# SCH_ZeeMini_-_2652p_Board_2021-08-10.net
KiCad netlist of a schematic drawn in EasyEDA
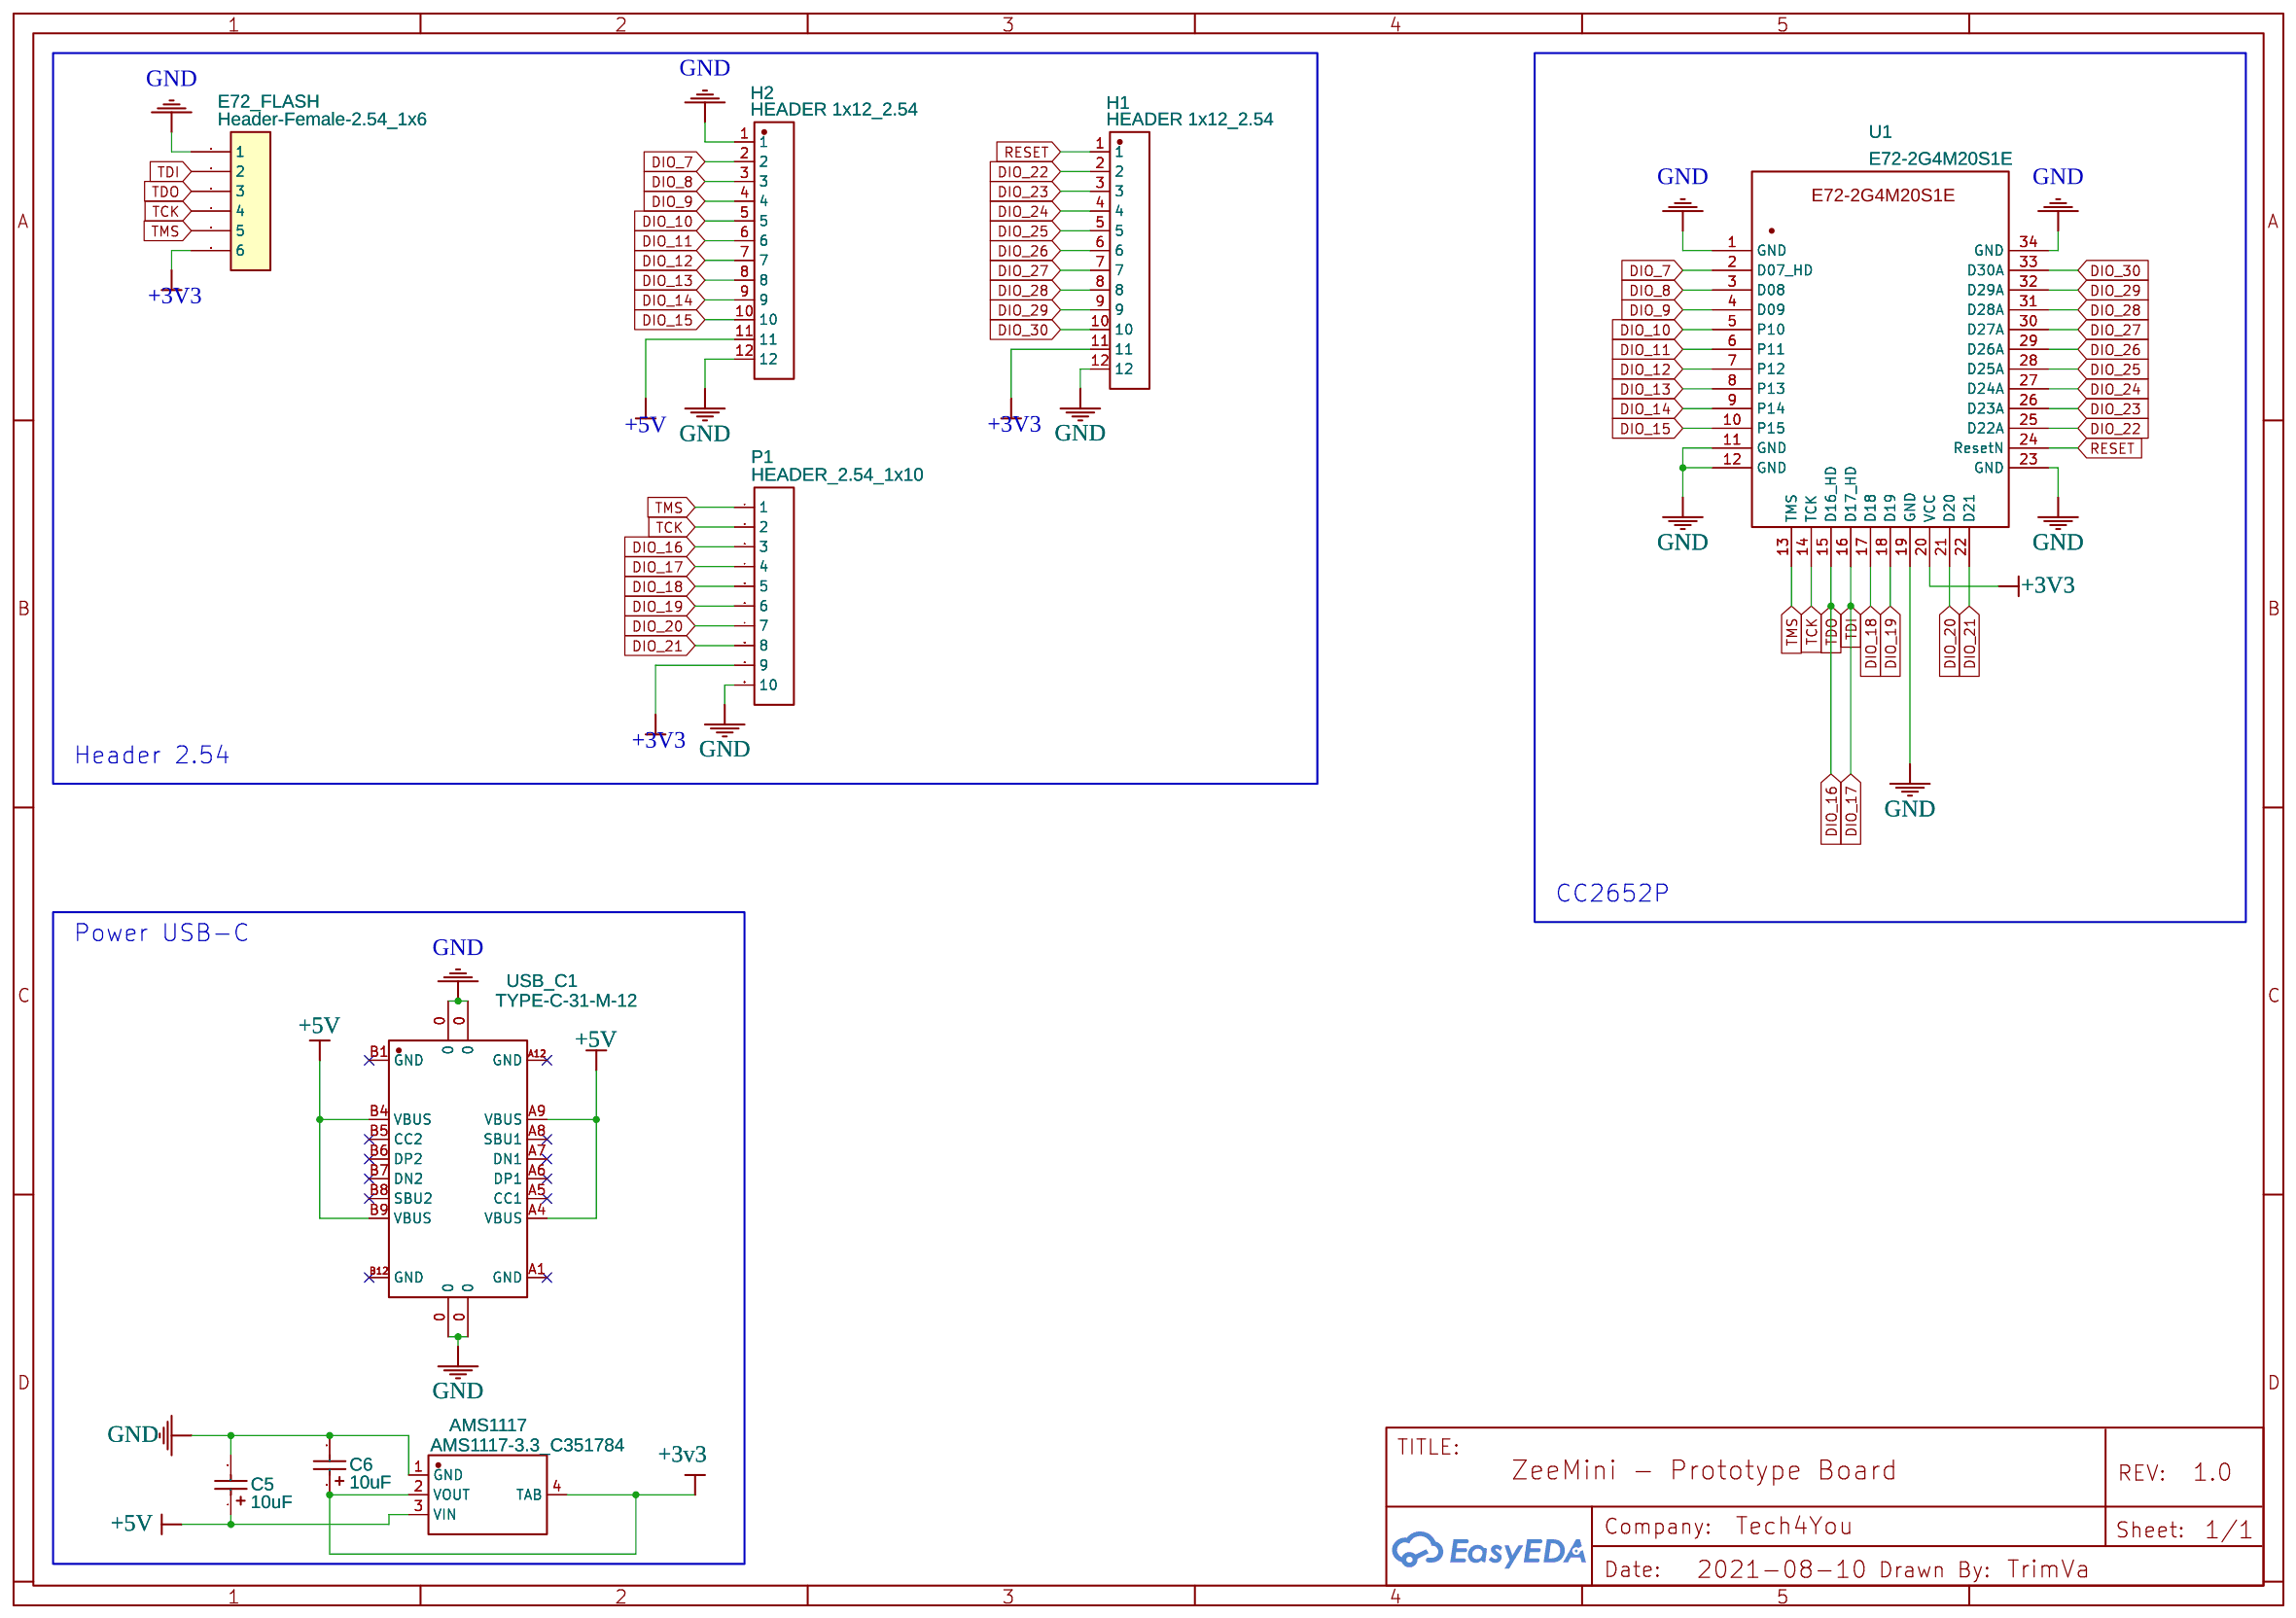
[diagram p0: schematic sheet]

(export (version "E")
  (design (tool "Eeschema 10.0.6"))
  (components
    (comp (ref "AMS1117")
      (value "AMS1117-3.3_C351784")
      (fields
        (field (name "BOM_Manufacturer Part") "AMS1117-3.3")
        (field (name "BOM_Supplier Part") "C351784")
      )
      (libsource (lib "") (part "AMS1117-3.3_C351784"))
    )
    (comp (ref "C5")
      (value "10uF")
      (fields
        (field (name "BOM_Manufacturer Part") "TAJA106K016RNJ")
        (field (name "BOM_Supplier Part") "C7171")
      )
      (libsource (lib "") (part "TAJA106K016RNJ"))
    )
    (comp (ref "C6")
      (value "10uF")
      (fields
        (field (name "BOM_Manufacturer Part") "TAJA106K016RNJ")
        (field (name "BOM_Supplier Part") "C7171")
      )
      (libsource (lib "") (part "TAJA106K016RNJ"))
    )
    (comp (ref "E72_FLASH")
      (value "Header-Female-2.54_1x6")
      (fields (field (name "BOM_Manufacturer Part") "Female header/2.54mm2x3 Female header"))
      (libsource (lib "") (part "Header-Female-2.54_1x6"))
    )
    (comp (ref "H1") (value "HEADER 1x12_2.54") (libsource (lib "") (part "HEADER 1x12_2.54")))
    (comp (ref "H2") (value "HEADER 1x12_2.54") (libsource (lib "") (part "HEADER 1x12_2.54")))
    (comp (ref "P1")
      (value "HEADER_2.54_1x10")
      (fields
        (field (name "BOM_Manufacturer Part") "Header-Male-2.54_1x6")
        (field (name "BOM_Supplier Part") "C37208")
      )
      (libsource (lib "") (part "HEADER_2.54_1x10"))
    )
    (comp (ref "U1") (value "E72-2G4M20S1E") (libsource (lib "") (part "E72-2G4M20S1E")))
    (comp (ref "USB_C1")
      (value "TYPE-C-31-M-12")
      (fields (field (name "BOM_Supplier Part") "C165948"))
      (libsource (lib "") (part "TYPE-C-31-M-12"))
    )
  )
  (nets
    (net (code "1") (name "+3V3") (class "Default")
      (node (ref "E72_FLASH") (pin "6") (pinfunction "6_6") (pintype "input"))
      (node (ref "H1") (pin "11") (pinfunction "11_11") (pintype "unspecified"))
      (node (ref "P1") (pin "9") (pinfunction "9_9") (pintype "input"))
      (node (ref "U1") (pin "20") (pinfunction "VCC_20") (pintype "passive"))
    )
    (net (code "2") (name "+3v3") (class "Default")
      (node (ref "AMS1117") (pin "2") (pinfunction "VOUT_2") (pintype "unspecified"))
      (node (ref "AMS1117") (pin "4") (pinfunction "TAB_4") (pintype "unspecified"))
      (node (ref "C6") (pin "1") (pinfunction "1_1") (pintype "input"))
    )
    (net (code "3") (name "+5V") (class "Default")
      (node (ref "AMS1117") (pin "3") (pinfunction "VIN_3") (pintype "unspecified"))
      (node (ref "C5") (pin "1") (pinfunction "1_1") (pintype "input"))
      (node (ref "H2") (pin "11") (pinfunction "11_11") (pintype "unspecified"))
      (node (ref "USB_C1") (pin "A4") (pinfunction "VBUS_A4") (pintype "unspecified"))
      (node (ref "USB_C1") (pin "A9") (pinfunction "VBUS_A9") (pintype "unspecified"))
      (node (ref "USB_C1") (pin "B4") (pinfunction "VBUS_B4") (pintype "unspecified"))
      (node (ref "USB_C1") (pin "B9") (pinfunction "VBUS_B9") (pintype "unspecified"))
    )
    (net (code "4") (name "DIO_7") (class "Default")
      (node (ref "H2") (pin "2") (pinfunction "2_2") (pintype "unspecified"))
      (node (ref "U1") (pin "2") (pinfunction "D07_HD_2") (pintype "bidirectional"))
    )
    (net (code "5") (name "DIO_8") (class "Default")
      (node (ref "H2") (pin "3") (pinfunction "3_3") (pintype "unspecified"))
      (node (ref "U1") (pin "3") (pinfunction "D08_3") (pintype "bidirectional"))
    )
    (net (code "6") (name "DIO_9") (class "Default")
      (node (ref "H2") (pin "4") (pinfunction "4_4") (pintype "unspecified"))
      (node (ref "U1") (pin "4") (pinfunction "D09_4") (pintype "bidirectional"))
    )
    (net (code "7") (name "DIO_10") (class "Default")
      (node (ref "H2") (pin "5") (pinfunction "5_5") (pintype "unspecified"))
      (node (ref "U1") (pin "5") (pinfunction "P10_5") (pintype "bidirectional"))
    )
    (net (code "8") (name "DIO_11") (class "Default")
      (node (ref "H2") (pin "6") (pinfunction "6_6") (pintype "unspecified"))
      (node (ref "U1") (pin "6") (pinfunction "P11_6") (pintype "bidirectional"))
    )
    (net (code "9") (name "DIO_12") (class "Default")
      (node (ref "H2") (pin "7") (pinfunction "7_7") (pintype "unspecified"))
      (node (ref "U1") (pin "7") (pinfunction "P12_7") (pintype "bidirectional"))
    )
    (net (code "10") (name "DIO_13") (class "Default")
      (node (ref "H2") (pin "8") (pinfunction "8_8") (pintype "unspecified"))
      (node (ref "U1") (pin "8") (pinfunction "P13_8") (pintype "bidirectional"))
    )
    (net (code "11") (name "DIO_14") (class "Default")
      (node (ref "H2") (pin "9") (pinfunction "9_9") (pintype "unspecified"))
      (node (ref "U1") (pin "9") (pinfunction "P14_9") (pintype "bidirectional"))
    )
    (net (code "12") (name "DIO_15") (class "Default")
      (node (ref "H2") (pin "10") (pinfunction "10_10") (pintype "unspecified"))
      (node (ref "U1") (pin "10") (pinfunction "P15_10") (pintype "bidirectional"))
    )
    (net (code "13") (name "DIO_16") (class "Default")
      (node (ref "E72_FLASH") (pin "3") (pinfunction "3_3") (pintype "input"))
      (node (ref "P1") (pin "3") (pinfunction "3_3") (pintype "input"))
      (node (ref "U1") (pin "15") (pinfunction "D16_HD_15") (pintype "bidirectional"))
    )
    (net (code "14") (name "DIO_17") (class "Default")
      (node (ref "E72_FLASH") (pin "2") (pinfunction "2_2") (pintype "input"))
      (node (ref "P1") (pin "4") (pinfunction "4_4") (pintype "input"))
      (node (ref "U1") (pin "16") (pinfunction "D17_HD_16") (pintype "bidirectional"))
    )
    (net (code "15") (name "DIO_18") (class "Default")
      (node (ref "P1") (pin "5") (pinfunction "5_5") (pintype "input"))
      (node (ref "U1") (pin "17") (pinfunction "D18_17") (pintype "bidirectional"))
    )
    (net (code "16") (name "DIO_19") (class "Default")
      (node (ref "P1") (pin "6") (pinfunction "6_6") (pintype "input"))
      (node (ref "U1") (pin "18") (pinfunction "D19_18") (pintype "bidirectional"))
    )
    (net (code "17") (name "DIO_20") (class "Default")
      (node (ref "P1") (pin "7") (pinfunction "7_7") (pintype "input"))
      (node (ref "U1") (pin "21") (pinfunction "D20_21") (pintype "bidirectional"))
    )
    (net (code "18") (name "DIO_21") (class "Default")
      (node (ref "P1") (pin "8") (pinfunction "8_8") (pintype "input"))
      (node (ref "U1") (pin "22") (pinfunction "D21_22") (pintype "bidirectional"))
    )
    (net (code "19") (name "DIO_22") (class "Default")
      (node (ref "H1") (pin "2") (pinfunction "2_2") (pintype "unspecified"))
      (node (ref "U1") (pin "25") (pinfunction "D22A_25") (pintype "bidirectional"))
    )
    (net (code "20") (name "DIO_23") (class "Default")
      (node (ref "H1") (pin "3") (pinfunction "3_3") (pintype "unspecified"))
      (node (ref "U1") (pin "26") (pinfunction "D23A_26") (pintype "bidirectional"))
    )
    (net (code "21") (name "DIO_24") (class "Default")
      (node (ref "H1") (pin "4") (pinfunction "4_4") (pintype "unspecified"))
      (node (ref "U1") (pin "27") (pinfunction "D24A_27") (pintype "bidirectional"))
    )
    (net (code "22") (name "DIO_25") (class "Default")
      (node (ref "H1") (pin "5") (pinfunction "5_5") (pintype "unspecified"))
      (node (ref "U1") (pin "28") (pinfunction "D25A_28") (pintype "bidirectional"))
    )
    (net (code "23") (name "DIO_26") (class "Default")
      (node (ref "H1") (pin "6") (pinfunction "6_6") (pintype "unspecified"))
      (node (ref "U1") (pin "29") (pinfunction "D26A_29") (pintype "bidirectional"))
    )
    (net (code "24") (name "DIO_27") (class "Default")
      (node (ref "H1") (pin "7") (pinfunction "7_7") (pintype "unspecified"))
      (node (ref "U1") (pin "30") (pinfunction "D27A_30") (pintype "bidirectional"))
    )
    (net (code "25") (name "DIO_28") (class "Default")
      (node (ref "H1") (pin "8") (pinfunction "8_8") (pintype "unspecified"))
      (node (ref "U1") (pin "31") (pinfunction "D28A_31") (pintype "bidirectional"))
    )
    (net (code "26") (name "DIO_29") (class "Default")
      (node (ref "H1") (pin "9") (pinfunction "9_9") (pintype "unspecified"))
      (node (ref "U1") (pin "32") (pinfunction "D29A_32") (pintype "bidirectional"))
    )
    (net (code "27") (name "DIO_30") (class "Default")
      (node (ref "H1") (pin "10") (pinfunction "10_10") (pintype "unspecified"))
      (node (ref "U1") (pin "33") (pinfunction "D30A_33") (pintype "bidirectional"))
    )
    (net (code "28") (name "GND") (class "Default")
      (node (ref "AMS1117") (pin "1") (pinfunction "GND_1") (pintype "unspecified"))
      (node (ref "C5") (pin "2") (pinfunction "2_2") (pintype "input"))
      (node (ref "C6") (pin "2") (pinfunction "2_2") (pintype "input"))
      (node (ref "E72_FLASH") (pin "1") (pinfunction "1_1") (pintype "input"))
      (node (ref "H1") (pin "12") (pinfunction "12_12") (pintype "unspecified"))
      (node (ref "H2") (pin "1") (pinfunction "1_1") (pintype "unspecified"))
      (node (ref "H2") (pin "12") (pinfunction "12_12") (pintype "unspecified"))
      (node (ref "P1") (pin "10") (pinfunction "10_10") (pintype "input"))
      (node (ref "U1") (pin "1") (pinfunction "GND_1") (pintype "passive"))
      (node (ref "U1") (pin "11") (pinfunction "GND_11") (pintype "passive"))
      (node (ref "U1") (pin "12") (pinfunction "GND_12") (pintype "passive"))
      (node (ref "U1") (pin "19") (pinfunction "GND_19") (pintype "passive"))
      (node (ref "U1") (pin "23") (pinfunction "GND_23") (pintype "passive"))
      (node (ref "U1") (pin "34") (pinfunction "GND_34") (pintype "passive"))
      (node (ref "USB_C1") (pin "0") (pinfunction "0_0") (pintype "unspecified"))
    )
    (net (code "29") (name "RESET") (class "Default")
      (node (ref "H1") (pin "1") (pinfunction "1_1") (pintype "unspecified"))
      (node (ref "U1") (pin "24") (pinfunction "ResetN_24") (pintype "input"))
    )
    (net (code "30") (name "TCK") (class "Default")
      (node (ref "E72_FLASH") (pin "4") (pinfunction "4_4") (pintype "input"))
      (node (ref "P1") (pin "2") (pinfunction "2_2") (pintype "input"))
      (node (ref "U1") (pin "14") (pinfunction "TCK_14") (pintype "bidirectional"))
    )
    (net (code "31") (name "TMS") (class "Default")
      (node (ref "E72_FLASH") (pin "5") (pinfunction "5_5") (pintype "input"))
      (node (ref "P1") (pin "1") (pinfunction "1_1") (pintype "input"))
      (node (ref "U1") (pin "13") (pinfunction "TMS_13") (pintype "bidirectional"))
    )
    (net (code "32") (name "unconnected-(USB_C1-CC1-PadA5)") (class "Default")
      (node (ref "USB_C1") (pin "A5") (pinfunction "CC1_A5") (pintype "unspecified+no_connect"))
    )
    (net (code "33") (name "unconnected-(USB_C1-CC2-PadB5)") (class "Default")
      (node (ref "USB_C1") (pin "B5") (pinfunction "CC2_B5") (pintype "unspecified+no_connect"))
    )
    (net (code "34") (name "unconnected-(USB_C1-DN1-PadA7)") (class "Default")
      (node (ref "USB_C1") (pin "A7") (pinfunction "DN1_A7") (pintype "unspecified+no_connect"))
    )
    (net (code "35") (name "unconnected-(USB_C1-DN2-PadB7)") (class "Default")
      (node (ref "USB_C1") (pin "B7") (pinfunction "DN2_B7") (pintype "unspecified+no_connect"))
    )
    (net (code "36") (name "unconnected-(USB_C1-DP1-PadA6)") (class "Default")
      (node (ref "USB_C1") (pin "A6") (pinfunction "DP1_A6") (pintype "unspecified+no_connect"))
    )
    (net (code "37") (name "unconnected-(USB_C1-DP2-PadB6)") (class "Default")
      (node (ref "USB_C1") (pin "B6") (pinfunction "DP2_B6") (pintype "unspecified+no_connect"))
    )
    (net (code "38") (name "unconnected-(USB_C1-GND-PadA1)") (class "Default")
      (node (ref "USB_C1") (pin "A1") (pinfunction "GND_A1") (pintype "unspecified+no_connect"))
    )
    (net (code "39") (name "unconnected-(USB_C1-GND-PadA12)") (class "Default")
      (node (ref "USB_C1") (pin "A12") (pinfunction "GND_A12") (pintype "unspecified+no_connect"))
    )
    (net (code "40") (name "unconnected-(USB_C1-GND-PadB1)") (class "Default")
      (node (ref "USB_C1") (pin "B1") (pinfunction "GND_B1") (pintype "unspecified+no_connect"))
    )
    (net (code "41") (name "unconnected-(USB_C1-GND-PadB12)") (class "Default")
      (node (ref "USB_C1") (pin "B12") (pinfunction "GND_B12") (pintype "unspecified+no_connect"))
    )
    (net (code "42") (name "unconnected-(USB_C1-SBU1-PadA8)") (class "Default")
      (node (ref "USB_C1") (pin "A8") (pinfunction "SBU1_A8") (pintype "unspecified+no_connect"))
    )
    (net (code "43") (name "unconnected-(USB_C1-SBU2-PadB8)") (class "Default")
      (node (ref "USB_C1") (pin "B8") (pinfunction "SBU2_B8") (pintype "unspecified+no_connect"))
    )
  )
)
